# USB-to-ESP-UART_v4_1.net
KiCad netlist of a schematic drawn in EAGLE
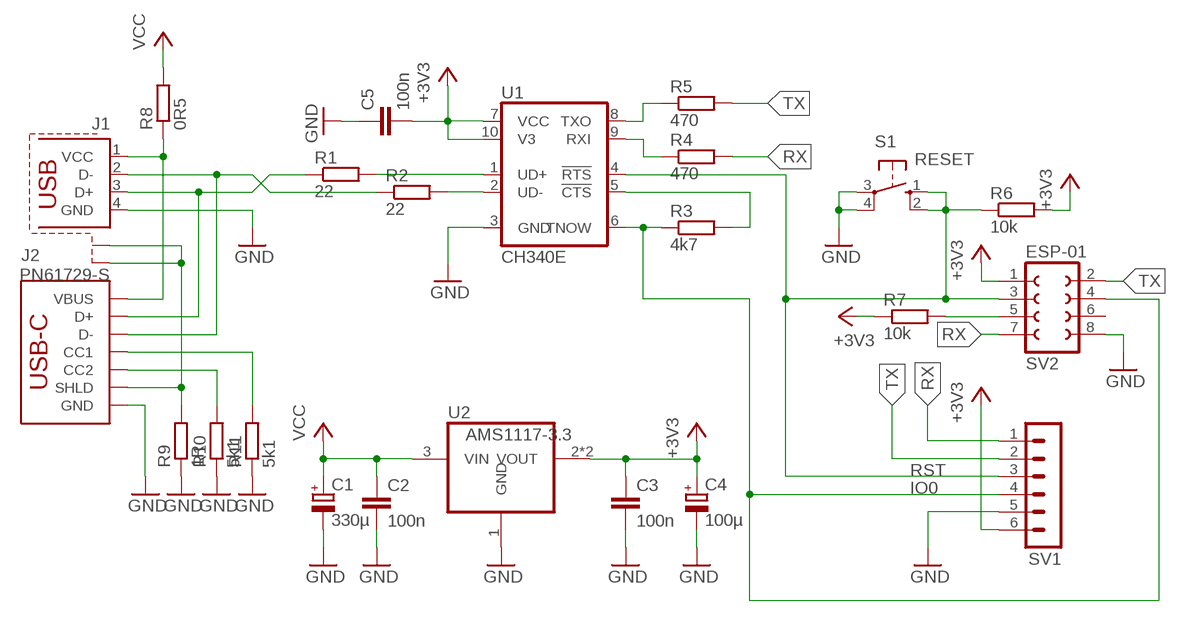
[diagram p0: schematic, sheet 1]

(export (version "E")
  (design (tool "Eeschema 10.0.6"))
  (components
    (comp (ref "C1")
      (value "330µ")
      (footprint "eagle-import:E2,5-7")
      (libsource (lib "eagle-import") (part "CPOL-EUE2.5-7"))
    )
    (comp (ref "C2")
      (value "100n")
      (footprint "eagle-import:C1206")
      (libsource (lib "eagle-import") (part "C-EUC1206"))
    )
    (comp (ref "C3")
      (value "100n")
      (footprint "eagle-import:C1206")
      (libsource (lib "eagle-import") (part "C-EUC1206"))
    )
    (comp (ref "C4")
      (value "100µ")
      (footprint "eagle-import:E2,5-5")
      (libsource (lib "eagle-import") (part "CPOL-EUE2.5-5"))
    )
    (comp (ref "C5")
      (value "100n")
      (footprint "eagle-import:C1206")
      (libsource (lib "eagle-import") (part "C-EUC1206"))
    )
    (comp (ref "J1")
      (value "PN61729-S")
      (footprint "eagle-import:PN61729-S")
      (libsource (lib "eagle-import") (part "PN61729-S"))
    )
    (comp (ref "J2")
      (value "USB_C_2-LAYER_PADS")
      (footprint "eagle-import:USB-C-16P-2LAYER-PADS")
      (libsource (lib "eagle-import") (part "USB_C_2-LAYER_PADS"))
    )
    (comp (ref "R1")
      (value "22")
      (footprint "eagle-import:R1206")
      (libsource (lib "eagle-import") (part "R-EU_R1206"))
    )
    (comp (ref "R2")
      (value "22")
      (footprint "eagle-import:R1206")
      (libsource (lib "eagle-import") (part "R-EU_R1206"))
    )
    (comp (ref "R3")
      (value "4k7")
      (footprint "eagle-import:R1206")
      (libsource (lib "eagle-import") (part "R-EU_R1206"))
    )
    (comp (ref "R4")
      (value "470")
      (footprint "eagle-import:R1206")
      (libsource (lib "eagle-import") (part "R-EU_R1206"))
    )
    (comp (ref "R5")
      (value "470")
      (footprint "eagle-import:R1206")
      (libsource (lib "eagle-import") (part "R-EU_R1206"))
    )
    (comp (ref "R6")
      (value "10k")
      (footprint "eagle-import:R1206")
      (libsource (lib "eagle-import") (part "R-EU_R1206"))
    )
    (comp (ref "R7")
      (value "10k")
      (footprint "eagle-import:R1206")
      (libsource (lib "eagle-import") (part "R-EU_R1206"))
    )
    (comp (ref "R8")
      (value "0R5")
      (footprint "eagle-import:R1206")
      (libsource (lib "eagle-import") (part "R-EU_R1206"))
    )
    (comp (ref "R9")
      (value "1R")
      (footprint "eagle-import:R1206")
      (libsource (lib "eagle-import") (part "R-EU_R1206"))
    )
    (comp (ref "R10")
      (value "5k1")
      (footprint "eagle-import:R1206")
      (libsource (lib "eagle-import") (part "R-EU_R1206"))
    )
    (comp (ref "R11")
      (value "5k1")
      (footprint "eagle-import:R1206")
      (libsource (lib "eagle-import") (part "R-EU_R1206"))
    )
    (comp (ref "S1")
      (value "RESET")
      (footprint "eagle-import:B3F-10XX")
      (fields (field (name "MPN") "B3F-1000"))
      (libsource (lib "eagle-import") (part "10-XX"))
    )
    (comp (ref "SV1")
      (value "MA06-1")
      (footprint "eagle-import:MA06-1")
      (libsource (lib "eagle-import") (part "MA06-1"))
    )
    (comp (ref "SV2")
      (value "ESP-01")
      (footprint "eagle-import:FE04-2-CL")
      (libsource (lib "eagle-import") (part "FE04-2CLEAN"))
    )
    (comp (ref "U1")
      (value "CH340E")
      (footprint "eagle-import:MSOP10")
      (fields (field (name "MF") "WCH"))
      (libsource (lib "eagle-import") (part "CH340E_MSOP10"))
    )
    (comp (ref "U2")
      (value "AMS1117-3.3")
      (footprint "eagle-import:SOT223")
      (fields (field (name "MPN") "REG1117"))
      (libsource (lib "eagle-import") (part "REG1117"))
    )
  )
  (nets
    (net (code "1") (name "+3V3") (class "Default")
      (node (ref "C3") (pin "1") (pinfunction "1_1") (pintype "passive"))
      (node (ref "C4") (pin "+") (pinfunction "+_+") (pintype "passive"))
      (node (ref "C5") (pin "2") (pinfunction "2_2") (pintype "passive"))
      (node (ref "R6") (pin "2") (pinfunction "2_2") (pintype "passive"))
      (node (ref "R7") (pin "1") (pinfunction "1_1") (pintype "passive"))
      (node (ref "SV1") (pin "6") (pinfunction "6_6") (pintype "passive"))
      (node (ref "SV2") (pin "1") (pinfunction "1_1") (pintype "passive"))
      (node (ref "U1") (pin "10") (pinfunction "V3_10") (pintype "bidirectional"))
      (node (ref "U1") (pin "7") (pinfunction "VCC_7") (pintype "bidirectional"))
      (node (ref "U2") (pin "2") (pinfunction "VOUT_2") (pintype "output"))
      (node (ref "U2") (pin "4") (pinfunction "VOUT_4") (pintype "output"))
    )
    (net (code "2") (name "/IO0") (class "Default")
      (node (ref "R3") (pin "1") (pinfunction "1_1") (pintype "passive"))
      (node (ref "SV1") (pin "4") (pinfunction "4_4") (pintype "passive"))
      (node (ref "SV2") (pin "4") (pinfunction "4_4") (pintype "passive"))
      (node (ref "U1") (pin "6") (pinfunction "TNOW_6") (pintype "bidirectional"))
    )
    (net (code "3") (name "/RST") (class "Default")
      (node (ref "R6") (pin "1") (pinfunction "1_1") (pintype "passive"))
      (node (ref "S1") (pin "1") (pinfunction "S_1") (pintype "passive"))
      (node (ref "S1") (pin "2") (pinfunction "S1_2") (pintype "passive"))
      (node (ref "SV1") (pin "3") (pinfunction "3_3") (pintype "passive"))
      (node (ref "SV2") (pin "3") (pinfunction "3_3") (pintype "passive"))
      (node (ref "U1") (pin "4") (pinfunction "~{RTS}_4") (pintype "bidirectional"))
    )
    (net (code "4") (name "GND") (class "Default")
      (node (ref "C1") (pin "-") (pinfunction "-_-") (pintype "passive"))
      (node (ref "C2") (pin "2") (pinfunction "2_2") (pintype "passive"))
      (node (ref "C3") (pin "2") (pinfunction "2_2") (pintype "passive"))
      (node (ref "C4") (pin "-") (pinfunction "-_-") (pintype "passive"))
      (node (ref "C5") (pin "1") (pinfunction "1_1") (pintype "passive"))
      (node (ref "J1") (pin "4") (pinfunction "GND_4") (pintype "passive"))
      (node (ref "J2") (pin "GND") (pinfunction "GND_GND") (pintype "bidirectional"))
      (node (ref "J2") (pin "GND2") (pinfunction "GND_GND2") (pintype "bidirectional"))
      (node (ref "R10") (pin "1") (pinfunction "1_1") (pintype "passive"))
      (node (ref "R11") (pin "1") (pinfunction "1_1") (pintype "passive"))
      (node (ref "R9") (pin "1") (pinfunction "1_1") (pintype "passive"))
      (node (ref "S1") (pin "3") (pinfunction "P_3") (pintype "passive"))
      (node (ref "S1") (pin "4") (pinfunction "P1_4") (pintype "passive"))
      (node (ref "SV1") (pin "5") (pinfunction "5_5") (pintype "passive"))
      (node (ref "SV2") (pin "8") (pinfunction "8_8") (pintype "passive"))
      (node (ref "U1") (pin "3") (pinfunction "GND_3") (pintype "bidirectional"))
      (node (ref "U2") (pin "1") (pinfunction "GND_1") (pintype "power_in"))
    )
    (net (code "5") (name "Net-(J1-D+)") (class "Default")
      (node (ref "J1") (pin "3") (pinfunction "D+_3") (pintype "passive"))
      (node (ref "J2") (pin "A6") (pinfunction "D+_A6") (pintype "bidirectional"))
      (node (ref "J2") (pin "B6") (pinfunction "D+_B6") (pintype "bidirectional"))
      (node (ref "R1") (pin "1") (pinfunction "1_1") (pintype "passive"))
    )
    (net (code "6") (name "Net-(J1-D-)") (class "Default")
      (node (ref "J1") (pin "2") (pinfunction "D-_2") (pintype "passive"))
      (node (ref "J2") (pin "A7") (pinfunction "D-_A7") (pintype "bidirectional"))
      (node (ref "J2") (pin "B7") (pinfunction "D-_B7") (pintype "bidirectional"))
      (node (ref "R2") (pin "1") (pinfunction "1_1") (pintype "passive"))
    )
    (net (code "7") (name "Net-(J1-PadS1)") (class "Default")
      (node (ref "J1") (pin "S1") (pinfunction "S1_S1") (pintype "passive"))
      (node (ref "J1") (pin "S2") (pinfunction "S2_S2") (pintype "passive"))
      (node (ref "J2") (pin "SHLD1") (pinfunction "SHLD_SHLD1") (pintype "bidirectional"))
      (node (ref "J2") (pin "SHLD2") (pinfunction "SHLD_SHLD2") (pintype "bidirectional"))
      (node (ref "J2") (pin "SHLD3") (pinfunction "SHLD_SHLD3") (pintype "bidirectional"))
      (node (ref "J2") (pin "SHLD4") (pinfunction "SHLD_SHLD4") (pintype "bidirectional"))
      (node (ref "R9") (pin "2") (pinfunction "2_2") (pintype "passive"))
    )
    (net (code "8") (name "Net-(J1-VCC)") (class "Default")
      (node (ref "J1") (pin "1") (pinfunction "VCC_1") (pintype "passive"))
      (node (ref "J2") (pin "VBUS1") (pinfunction "VBUS_VBUS1") (pintype "bidirectional"))
      (node (ref "J2") (pin "VBUS2") (pinfunction "VBUS_VBUS2") (pintype "bidirectional"))
      (node (ref "R8") (pin "1") (pinfunction "1_1") (pintype "passive"))
    )
    (net (code "9") (name "Net-(J2-CC1)") (class "Default")
      (node (ref "J2") (pin "A5") (pinfunction "CC1_A5") (pintype "bidirectional"))
      (node (ref "R11") (pin "2") (pinfunction "2_2") (pintype "passive"))
    )
    (net (code "10") (name "Net-(J2-CC2)") (class "Default")
      (node (ref "J2") (pin "B5") (pinfunction "CC2_B5") (pintype "bidirectional"))
      (node (ref "R10") (pin "2") (pinfunction "2_2") (pintype "passive"))
    )
    (net (code "11") (name "Net-(R7-Pad2)") (class "Default")
      (node (ref "R7") (pin "2") (pinfunction "2_2") (pintype "passive"))
      (node (ref "SV2") (pin "5") (pinfunction "5_5") (pintype "passive"))
    )
    (net (code "12") (name "Net-(U1-RXI)") (class "Default")
      (node (ref "R4") (pin "1") (pinfunction "1_1") (pintype "passive"))
      (node (ref "U1") (pin "9") (pinfunction "RXI_9") (pintype "bidirectional"))
    )
    (net (code "13") (name "Net-(U1-TXO)") (class "Default")
      (node (ref "R5") (pin "1") (pinfunction "1_1") (pintype "passive"))
      (node (ref "U1") (pin "8") (pinfunction "TXO_8") (pintype "bidirectional"))
    )
    (net (code "14") (name "Net-(U1-UD+)") (class "Default")
      (node (ref "R1") (pin "2") (pinfunction "2_2") (pintype "passive"))
      (node (ref "U1") (pin "1") (pinfunction "UD+_1") (pintype "bidirectional"))
    )
    (net (code "15") (name "Net-(U1-UD-)") (class "Default")
      (node (ref "R2") (pin "2") (pinfunction "2_2") (pintype "passive"))
      (node (ref "U1") (pin "2") (pinfunction "UD-_2") (pintype "bidirectional"))
    )
    (net (code "16") (name "Net-(U1-~{CTS})") (class "Default")
      (node (ref "R3") (pin "2") (pinfunction "2_2") (pintype "passive"))
      (node (ref "U1") (pin "5") (pinfunction "~{CTS}_5") (pintype "bidirectional"))
    )
    (net (code "17") (name "RX") (class "Default")
      (node (ref "R4") (pin "2") (pinfunction "2_2") (pintype "passive"))
      (node (ref "SV1") (pin "1") (pinfunction "1_1") (pintype "passive"))
      (node (ref "SV2") (pin "7") (pinfunction "7_7") (pintype "passive"))
    )
    (net (code "18") (name "TX") (class "Default")
      (node (ref "R5") (pin "2") (pinfunction "2_2") (pintype "passive"))
      (node (ref "SV1") (pin "2") (pinfunction "2_2") (pintype "passive"))
      (node (ref "SV2") (pin "2") (pinfunction "2_2") (pintype "passive"))
    )
    (net (code "19") (name "VCC") (class "Default")
      (node (ref "C1") (pin "+") (pinfunction "+_+") (pintype "passive"))
      (node (ref "C2") (pin "1") (pinfunction "1_1") (pintype "passive"))
      (node (ref "R8") (pin "2") (pinfunction "2_2") (pintype "passive"))
      (node (ref "U2") (pin "3") (pinfunction "VIN_3") (pintype "input"))
    )
    (net (code "20") (name "unconnected-(SV2-Pad6)") (class "Default")
      (node (ref "SV2") (pin "6") (pinfunction "6_6") (pintype "passive"))
    )
  )
)
